# QCopterFly_EXTERN_Sch.net
KiCad netlist of a schematic drawn in Altium Designer
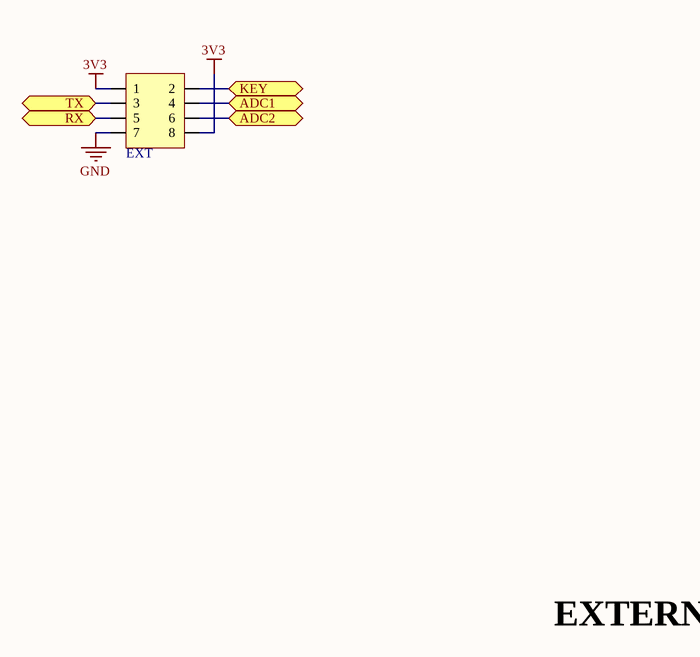
[diagram p0: QCopterFly_EXTERN_Sch.SchDoc]

(export (version "E")
  (design (tool "Eeschema 10.0.6"))
  (components
    (comp (ref "EXT")
      (value "HDR2X4_90_2.54")
      (footprint "PCB_Connector:HDR2X4_90_2.54")
      (description "Header")
      (libsource (lib "SCH_Connector") (part "HDR2X4_90_2.54"))
    )
  )
  (nets
    (net (code "1") (name "/ADC1") (class "Default")
      (node (ref "EXT") (pin "4") (pinfunction "4_4") (pintype "passive"))
    )
    (net (code "2") (name "/ADC2") (class "Default")
      (node (ref "EXT") (pin "6") (pinfunction "6_6") (pintype "passive"))
    )
    (net (code "4") (name "/KEY") (class "Default")
      (node (ref "EXT") (pin "2") (pinfunction "2_2") (pintype "passive"))
    )
    (net (code "5") (name "/RX") (class "Default")
      (node (ref "EXT") (pin "5") (pinfunction "5_5") (pintype "passive"))
    )
    (net (code "6") (name "/TX") (class "Default")
      (node (ref "EXT") (pin "3") (pinfunction "3_3") (pintype "passive"))
    )
    (net (code "7") (name "3V3") (class "Default")
      (node (ref "EXT") (pin "1") (pinfunction "1_1") (pintype "passive"))
      (node (ref "EXT") (pin "8") (pinfunction "8_8") (pintype "passive"))
    )
    (net (code "8") (name "GND") (class "Default")
      (node (ref "EXT") (pin "7") (pinfunction "7_7") (pintype "passive"))
    )
  )
)
